# LCD1602.net
KiCad netlist of a schematic drawn in Altium Designer
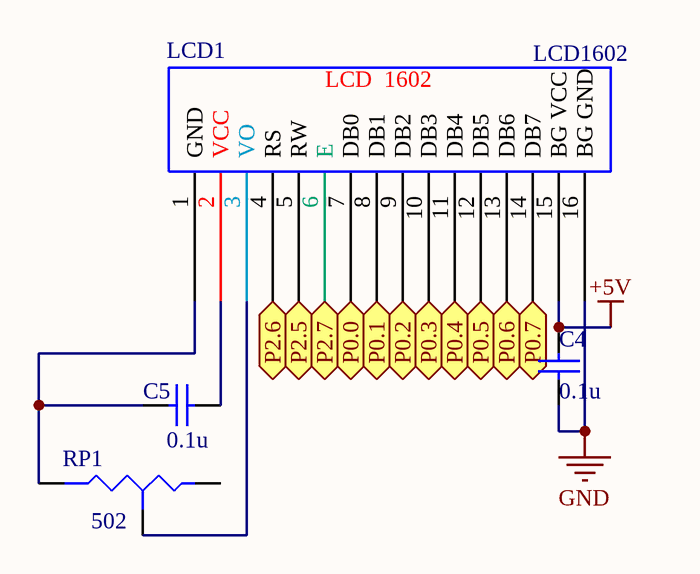
[diagram p0: LCD1602液晶显示.SchDoc]

(export (version "E")
  (design (tool "Eeschema 10.0.6"))
  (components
    (comp (ref "C4")
      (value "瓷片电容")
      (footprint "瓷片电容")
      (fields (field (name "ALTIUM_UNNAMED_1") "0.1u"))
      (libsource (lib "自制库（原理图文件）") (part "瓷片电容"))
    )
    (comp (ref "C5")
      (value "瓷片电容")
      (footprint "瓷片电容")
      (fields (field (name "ALTIUM_UNNAMED_1") "0.1u"))
      (libsource (lib "自制库（原理图文件）") (part "瓷片电容"))
    )
    (comp (ref "LCD1") (value "LCD1602") (footprint "SIP16") (libsource (lib "自制库（原理图文件）") (part "LCD1602")))
    (comp (ref "RP1")
      (value "滑阻")
      (footprint "三脚滑阻")
      (fields (field (name "ALTIUM_UNNAMED_1") "502"))
      (libsource (lib "自制库（原理图文件）") (part "滑阻"))
    )
  )
  (nets
    (net (code "1") (name "+5V") (class "Default")
      (node (ref "C4") (pin "1") (pinfunction "1_1") (pintype "passive"))
      (node (ref "LCD1") (pin "15") (pinfunction "BG_VCC_15") (pintype "passive"))
    )
    (net (code "2") (name "/P0.0") (class "Default")
      (node (ref "LCD1") (pin "7") (pinfunction "DB0_7") (pintype "passive"))
    )
    (net (code "3") (name "/P0.1") (class "Default")
      (node (ref "LCD1") (pin "8") (pinfunction "DB1_8") (pintype "passive"))
    )
    (net (code "4") (name "/P0.2") (class "Default")
      (node (ref "LCD1") (pin "9") (pinfunction "DB2_9") (pintype "passive"))
    )
    (net (code "5") (name "/P0.3") (class "Default")
      (node (ref "LCD1") (pin "10") (pinfunction "DB3_10") (pintype "passive"))
    )
    (net (code "6") (name "/P0.4") (class "Default")
      (node (ref "LCD1") (pin "11") (pinfunction "DB4_11") (pintype "passive"))
    )
    (net (code "7") (name "/P0.5") (class "Default")
      (node (ref "LCD1") (pin "12") (pinfunction "DB5_12") (pintype "passive"))
    )
    (net (code "8") (name "/P0.6") (class "Default")
      (node (ref "LCD1") (pin "13") (pinfunction "DB6_13") (pintype "passive"))
    )
    (net (code "9") (name "/P0.7") (class "Default")
      (node (ref "LCD1") (pin "14") (pinfunction "DB7_14") (pintype "passive"))
    )
    (net (code "10") (name "/P2.5") (class "Default")
      (node (ref "LCD1") (pin "5") (pinfunction "RW_5") (pintype "passive"))
    )
    (net (code "11") (name "/P2.6") (class "Default")
      (node (ref "LCD1") (pin "4") (pinfunction "RS_4") (pintype "passive"))
    )
    (net (code "12") (name "/P2.7") (class "Default")
      (node (ref "LCD1") (pin "6") (pinfunction "E_6") (pintype "passive"))
    )
    (net (code "13") (name "GND") (class "Default")
      (node (ref "C4") (pin "2") (pinfunction "2_2") (pintype "passive"))
      (node (ref "LCD1") (pin "16") (pinfunction "BG_GND_16") (pintype "passive"))
    )
    (net (code "14") (name "Net-(LCD1-GND)") (class "Default")
      (node (ref "C5") (pin "2") (pinfunction "2_2") (pintype "passive"))
      (node (ref "LCD1") (pin "1") (pinfunction "GND_1") (pintype "passive"))
      (node (ref "RP1") (pin "3") (pinfunction "B_3") (pintype "passive"))
    )
    (net (code "15") (name "Net-(LCD1-VCC)") (class "Default")
      (node (ref "C5") (pin "1") (pinfunction "1_1") (pintype "passive"))
      (node (ref "LCD1") (pin "2") (pinfunction "VCC_2") (pintype "passive"))
    )
    (net (code "16") (name "Net-(LCD1-VO)") (class "Default")
      (node (ref "LCD1") (pin "3") (pinfunction "VO_3") (pintype "passive"))
      (node (ref "RP1") (pin "2") (pinfunction "TAP_2") (pintype "passive"))
    )
    (net (code "17") (name "unconnected-(RP1-A-Pad1)") (class "Default")
      (node (ref "RP1") (pin "1") (pinfunction "A_1") (pintype "passive"))
    )
  )
)
